# PICDevBoard-V1RevA.net
KiCad netlist of a schematic drawn in EAGLE
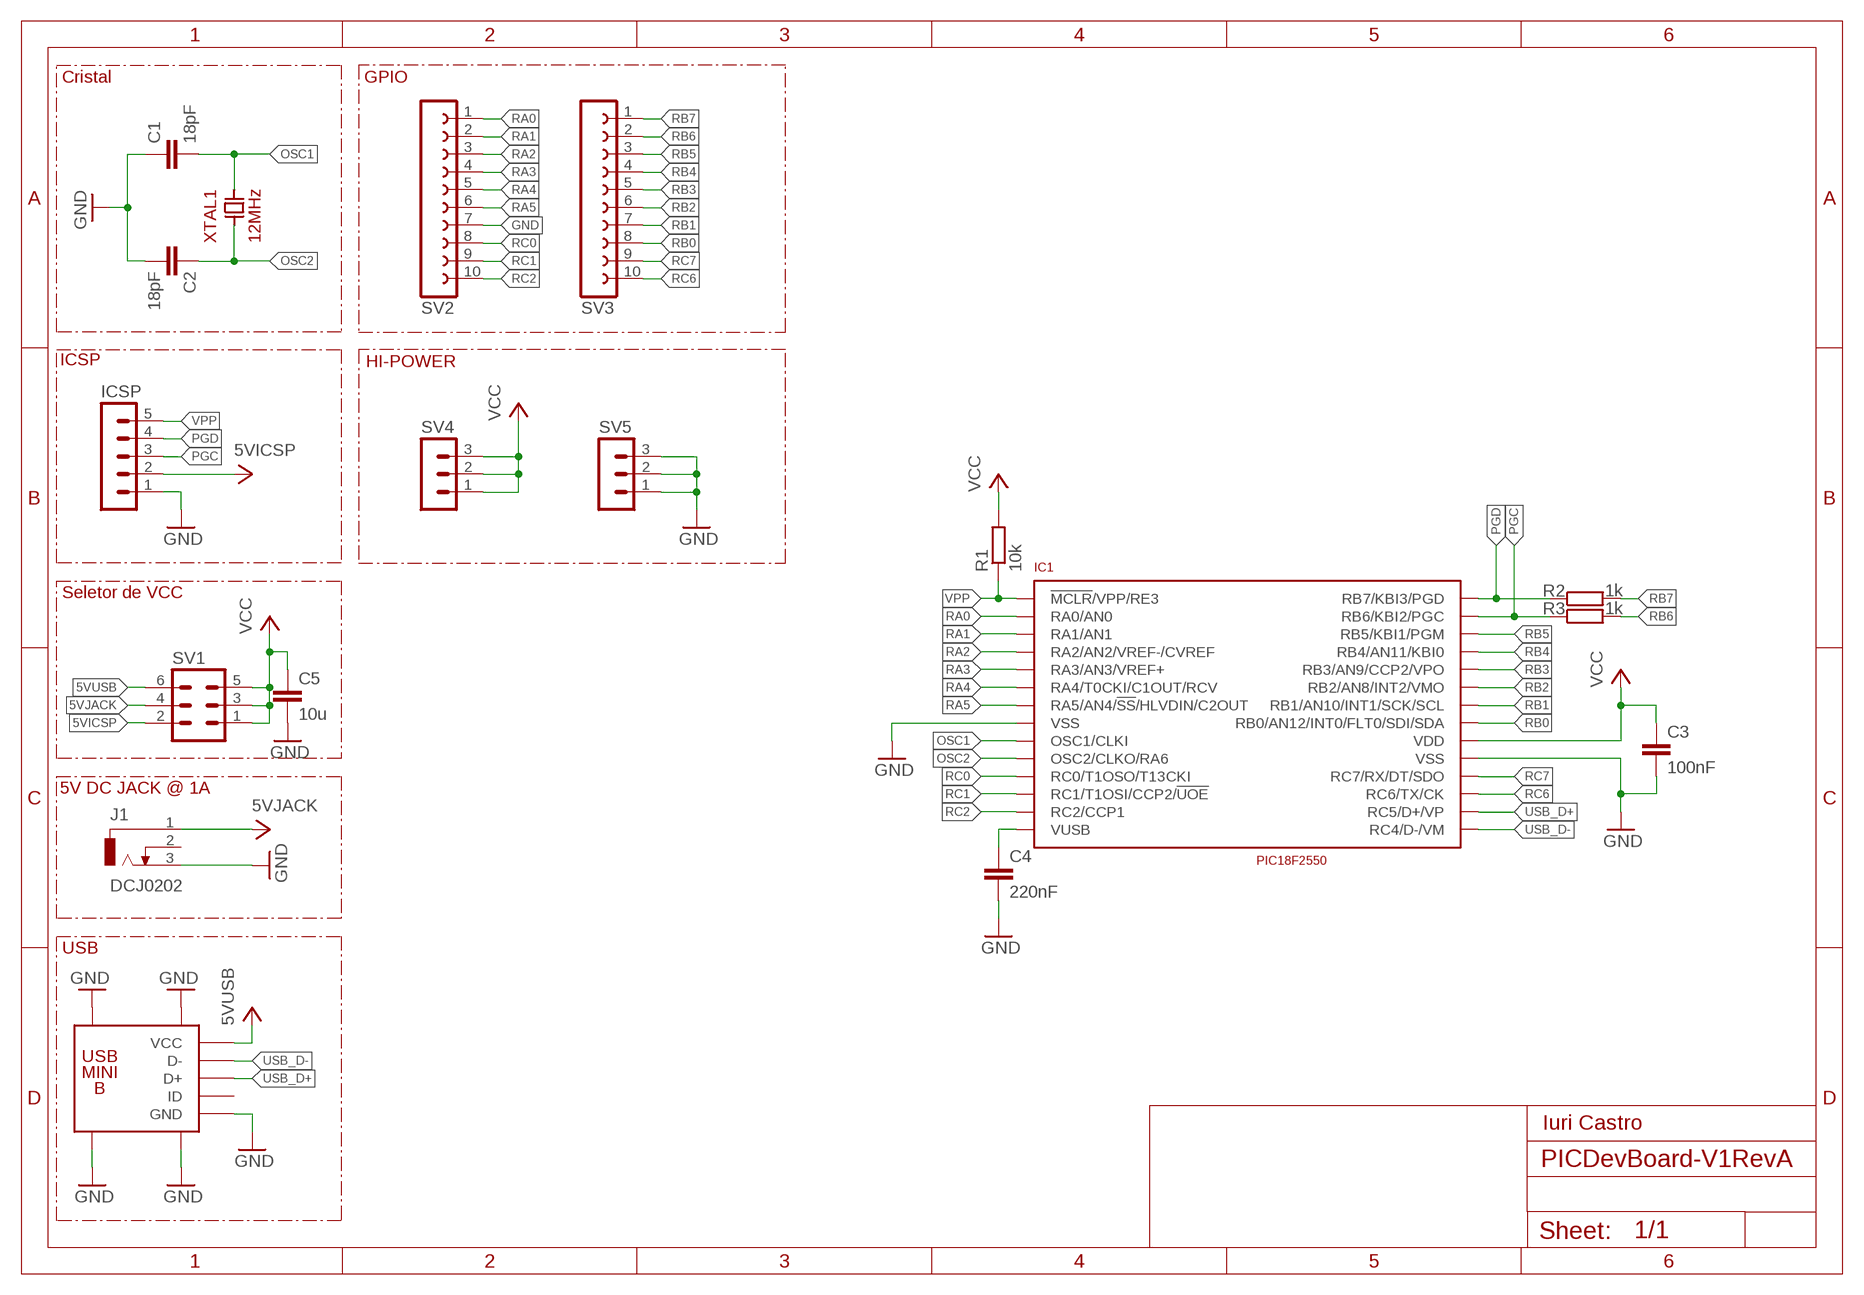
[diagram p0: schematic, sheet 1]

(export (version "E")
  (design (tool "Eeschema 10.0.6"))
  (components
    (comp (ref "C1")
      (value "18pF")
      (footprint "eagle-import:C0805")
      (libsource (lib "eagle-import") (part "C-EUC0805"))
    )
    (comp (ref "C2")
      (value "18pF")
      (footprint "eagle-import:C0805")
      (libsource (lib "eagle-import") (part "C-EUC0805"))
    )
    (comp (ref "C3")
      (value "100nF")
      (footprint "eagle-import:C0805")
      (libsource (lib "eagle-import") (part "C-EUC0805"))
    )
    (comp (ref "C4")
      (value "220nF")
      (footprint "eagle-import:C0805")
      (libsource (lib "eagle-import") (part "C-EUC0805"))
    )
    (comp (ref "C5")
      (value "10u")
      (footprint "eagle-import:C0805")
      (libsource (lib "eagle-import") (part "C-EUC0805"))
    )
    (comp (ref "IC1")
      (value "PIC18F2550")
      (footprint "eagle-import:DIL28-3")
      (libsource (lib "eagle-import") (part "PIC18F2550"))
    )
    (comp (ref "ICSP")
      (value "MA05-1")
      (footprint "eagle-import:MA05-1")
      (libsource (lib "eagle-import") (part "MA05-1"))
    )
    (comp (ref "J1")
      (value "DCJ0202")
      (footprint "eagle-import:DCJ0202")
      (libsource (lib "eagle-import") (part "DCJ0202"))
    )
    (comp (ref "R1")
      (value "10k")
      (footprint "eagle-import:R0805")
      (libsource (lib "eagle-import") (part "R-EU_R0805"))
    )
    (comp (ref "R2")
      (value "1k")
      (footprint "eagle-import:R0805")
      (libsource (lib "eagle-import") (part "R-EU_R0805"))
    )
    (comp (ref "R3")
      (value "1k")
      (footprint "eagle-import:R0805")
      (libsource (lib "eagle-import") (part "R-EU_R0805"))
    )
    (comp (ref "SV1")
      (value "MA03-2")
      (footprint "eagle-import:MA03-2")
      (libsource (lib "eagle-import") (part "MA03-2"))
    )
    (comp (ref "SV2")
      (value "FE10-1")
      (footprint "eagle-import:FE10")
      (libsource (lib "eagle-import") (part "FE10-1"))
    )
    (comp (ref "SV3")
      (value "FE10-1")
      (footprint "eagle-import:FE10")
      (libsource (lib "eagle-import") (part "FE10-1"))
    )
    (comp (ref "SV4")
      (value "MA03-1")
      (footprint "eagle-import:MA03-1")
      (libsource (lib "eagle-import") (part "MA03-1"))
    )
    (comp (ref "SV5")
      (value "MA03-1")
      (footprint "eagle-import:MA03-1")
      (libsource (lib "eagle-import") (part "MA03-1"))
    )
    (comp (ref "USB1")
      (value "USB-MINI-B")
      (footprint "eagle-import:DX2R005HN2E700")
      (libsource (lib "eagle-import") (part "USB-MINI-B"))
    )
    (comp (ref "XTAL1")
      (value "12MHz")
      (footprint "eagle-import:HC49-S")
      (libsource (lib "eagle-import") (part "HC49-S"))
    )
  )
  (nets
    (net (code "1") (name "5VICSP") (class "Default")
      (node (ref "ICSP") (pin "2") (pinfunction "2_2") (pintype "passive"))
      (node (ref "SV1") (pin "2") (pinfunction "2_2") (pintype "passive"))
    )
    (net (code "2") (name "5VJACK") (class "Default")
      (node (ref "J1") (pin "1") (pinfunction "1_1") (pintype "passive"))
      (node (ref "SV1") (pin "4") (pinfunction "4_4") (pintype "passive"))
    )
    (net (code "3") (name "5VUSB") (class "Default")
      (node (ref "SV1") (pin "6") (pinfunction "6_6") (pintype "passive"))
      (node (ref "USB1") (pin "P$1") (pinfunction "VCC_P$1") (pintype "bidirectional"))
    )
    (net (code "4") (name "GND") (class "Default")
      (node (ref "C1") (pin "1") (pinfunction "1_1") (pintype "passive"))
      (node (ref "C2") (pin "2") (pinfunction "2_2") (pintype "passive"))
      (node (ref "C3") (pin "2") (pinfunction "2_2") (pintype "passive"))
      (node (ref "C4") (pin "2") (pinfunction "2_2") (pintype "passive"))
      (node (ref "C5") (pin "2") (pinfunction "2_2") (pintype "passive"))
      (node (ref "IC1") (pin "19") (pinfunction "VSS_19") (pintype "bidirectional"))
      (node (ref "IC1") (pin "8") (pinfunction "VSS_8") (pintype "bidirectional"))
      (node (ref "ICSP") (pin "1") (pinfunction "1_1") (pintype "passive"))
      (node (ref "J1") (pin "3") (pinfunction "3_3") (pintype "passive"))
      (node (ref "SV2") (pin "7") (pinfunction "7_7") (pintype "passive"))
      (node (ref "SV5") (pin "1") (pinfunction "1_1") (pintype "passive"))
      (node (ref "SV5") (pin "2") (pinfunction "2_2") (pintype "passive"))
      (node (ref "SV5") (pin "3") (pinfunction "3_3") (pintype "passive"))
      (node (ref "USB1") (pin "P$5") (pinfunction "GND_P$5") (pintype "bidirectional"))
      (node (ref "USB1") (pin "P$6") (pinfunction "GND_P$6") (pintype "bidirectional"))
      (node (ref "USB1") (pin "P$7") (pinfunction "GND_P$7") (pintype "bidirectional"))
      (node (ref "USB1") (pin "P$8") (pinfunction "GND_P$8") (pintype "bidirectional"))
      (node (ref "USB1") (pin "P$9") (pinfunction "GND_P$9") (pintype "bidirectional"))
    )
    (net (code "5") (name "Net-(IC1-VUSB)") (class "Default")
      (node (ref "C4") (pin "1") (pinfunction "1_1") (pintype "passive"))
      (node (ref "IC1") (pin "14") (pinfunction "VUSB_14") (pintype "bidirectional"))
    )
    (net (code "6") (name "OSC1") (class "Default")
      (node (ref "C1") (pin "2") (pinfunction "2_2") (pintype "passive"))
      (node (ref "IC1") (pin "9") (pinfunction "OSC1/CLKI_9") (pintype "bidirectional"))
      (node (ref "XTAL1") (pin "P$2") (pinfunction "P$2_P$2") (pintype "bidirectional"))
    )
    (net (code "7") (name "OSC2") (class "Default")
      (node (ref "C2") (pin "1") (pinfunction "1_1") (pintype "passive"))
      (node (ref "IC1") (pin "10") (pinfunction "OSC2/CLKO/RA6_10") (pintype "bidirectional"))
      (node (ref "XTAL1") (pin "P$1") (pinfunction "P$1_P$1") (pintype "bidirectional"))
    )
    (net (code "8") (name "PGC") (class "Default")
      (node (ref "IC1") (pin "27") (pinfunction "RB6/KBI2/PGC_27") (pintype "bidirectional"))
      (node (ref "ICSP") (pin "3") (pinfunction "3_3") (pintype "passive"))
      (node (ref "R3") (pin "1") (pinfunction "1_1") (pintype "passive"))
    )
    (net (code "9") (name "PGD") (class "Default")
      (node (ref "IC1") (pin "28") (pinfunction "RB7/KBI3/PGD_28") (pintype "bidirectional"))
      (node (ref "ICSP") (pin "4") (pinfunction "4_4") (pintype "passive"))
      (node (ref "R2") (pin "1") (pinfunction "1_1") (pintype "passive"))
    )
    (net (code "10") (name "RA0") (class "Default")
      (node (ref "IC1") (pin "2") (pinfunction "RA0/AN0_2") (pintype "bidirectional"))
      (node (ref "SV2") (pin "1") (pinfunction "1_1") (pintype "passive"))
    )
    (net (code "11") (name "RA1") (class "Default")
      (node (ref "IC1") (pin "3") (pinfunction "RA1/AN1_3") (pintype "bidirectional"))
      (node (ref "SV2") (pin "2") (pinfunction "2_2") (pintype "passive"))
    )
    (net (code "12") (name "RA2") (class "Default")
      (node (ref "IC1") (pin "4") (pinfunction "RA2/AN2/VREF-/CVREF_4") (pintype "bidirectional"))
      (node (ref "SV2") (pin "3") (pinfunction "3_3") (pintype "passive"))
    )
    (net (code "13") (name "RA3") (class "Default")
      (node (ref "IC1") (pin "5") (pinfunction "RA3/AN3/VREF+_5") (pintype "bidirectional"))
      (node (ref "SV2") (pin "4") (pinfunction "4_4") (pintype "passive"))
    )
    (net (code "14") (name "RA4") (class "Default")
      (node (ref "IC1") (pin "6") (pinfunction "RA4/T0CKI/C1OUT/RCV_6") (pintype "bidirectional"))
      (node (ref "SV2") (pin "5") (pinfunction "5_5") (pintype "passive"))
    )
    (net (code "15") (name "RA5") (class "Default")
      (node (ref "IC1") (pin "7") (pinfunction "RA5/AN4/~{SS}/HLVDIN/C2OUT_7") (pintype "bidirectional"))
      (node (ref "SV2") (pin "6") (pinfunction "6_6") (pintype "passive"))
    )
    (net (code "16") (name "RB0") (class "Default")
      (node (ref "IC1") (pin "21") (pinfunction "RB0/AN12/INT0/FLT0/SDI/SDA_21") (pintype "bidirectional"))
      (node (ref "SV3") (pin "8") (pinfunction "8_8") (pintype "passive"))
    )
    (net (code "17") (name "RB1") (class "Default")
      (node (ref "IC1") (pin "22") (pinfunction "RB1/AN10/INT1/SCK/SCL_22") (pintype "bidirectional"))
      (node (ref "SV3") (pin "7") (pinfunction "7_7") (pintype "passive"))
    )
    (net (code "18") (name "RB2") (class "Default")
      (node (ref "IC1") (pin "23") (pinfunction "RB2/AN8/INT2/VMO_23") (pintype "bidirectional"))
      (node (ref "SV3") (pin "6") (pinfunction "6_6") (pintype "passive"))
    )
    (net (code "19") (name "RB3") (class "Default")
      (node (ref "IC1") (pin "24") (pinfunction "RB3/AN9/CCP2/VPO_24") (pintype "bidirectional"))
      (node (ref "SV3") (pin "5") (pinfunction "5_5") (pintype "passive"))
    )
    (net (code "20") (name "RB4") (class "Default")
      (node (ref "IC1") (pin "25") (pinfunction "RB4/AN11/KBI0_25") (pintype "bidirectional"))
      (node (ref "SV3") (pin "4") (pinfunction "4_4") (pintype "passive"))
    )
    (net (code "21") (name "RB5") (class "Default")
      (node (ref "IC1") (pin "26") (pinfunction "RB5/KBI1/PGM_26") (pintype "bidirectional"))
      (node (ref "SV3") (pin "3") (pinfunction "3_3") (pintype "passive"))
    )
    (net (code "22") (name "RB6") (class "Default")
      (node (ref "R3") (pin "2") (pinfunction "2_2") (pintype "passive"))
      (node (ref "SV3") (pin "2") (pinfunction "2_2") (pintype "passive"))
    )
    (net (code "23") (name "RB7") (class "Default")
      (node (ref "R2") (pin "2") (pinfunction "2_2") (pintype "passive"))
      (node (ref "SV3") (pin "1") (pinfunction "1_1") (pintype "passive"))
    )
    (net (code "24") (name "RC0") (class "Default")
      (node (ref "IC1") (pin "11") (pinfunction "RC0/T1OSO/T13CKI_11") (pintype "bidirectional"))
      (node (ref "SV2") (pin "8") (pinfunction "8_8") (pintype "passive"))
    )
    (net (code "25") (name "RC1") (class "Default")
      (node (ref "IC1") (pin "12") (pinfunction "RC1/T1OSI/CCP2/~{UOE}_12") (pintype "bidirectional"))
      (node (ref "SV2") (pin "9") (pinfunction "9_9") (pintype "passive"))
    )
    (net (code "26") (name "RC2") (class "Default")
      (node (ref "IC1") (pin "13") (pinfunction "RC2/CCP1_13") (pintype "bidirectional"))
      (node (ref "SV2") (pin "10") (pinfunction "10_10") (pintype "passive"))
    )
    (net (code "27") (name "RC6") (class "Default")
      (node (ref "IC1") (pin "17") (pinfunction "RC6/TX/CK_17") (pintype "bidirectional"))
      (node (ref "SV3") (pin "10") (pinfunction "10_10") (pintype "passive"))
    )
    (net (code "28") (name "RC7") (class "Default")
      (node (ref "IC1") (pin "18") (pinfunction "RC7/RX/DT/SDO_18") (pintype "bidirectional"))
      (node (ref "SV3") (pin "9") (pinfunction "9_9") (pintype "passive"))
    )
    (net (code "29") (name "USB_D+") (class "Default")
      (node (ref "IC1") (pin "16") (pinfunction "RC5/D+/VP_16") (pintype "bidirectional"))
      (node (ref "USB1") (pin "P$3") (pinfunction "D+_P$3") (pintype "bidirectional"))
    )
    (net (code "30") (name "USB_D-") (class "Default")
      (node (ref "IC1") (pin "15") (pinfunction "RC4/D-/VM_15") (pintype "bidirectional"))
      (node (ref "USB1") (pin "P$2") (pinfunction "D-_P$2") (pintype "bidirectional"))
    )
    (net (code "31") (name "VCC") (class "Default")
      (node (ref "C3") (pin "1") (pinfunction "1_1") (pintype "passive"))
      (node (ref "C5") (pin "1") (pinfunction "1_1") (pintype "passive"))
      (node (ref "IC1") (pin "20") (pinfunction "VDD_20") (pintype "bidirectional"))
      (node (ref "R1") (pin "2") (pinfunction "2_2") (pintype "passive"))
      (node (ref "SV1") (pin "1") (pinfunction "1_1") (pintype "passive"))
      (node (ref "SV1") (pin "3") (pinfunction "3_3") (pintype "passive"))
      (node (ref "SV1") (pin "5") (pinfunction "5_5") (pintype "passive"))
      (node (ref "SV4") (pin "1") (pinfunction "1_1") (pintype "passive"))
      (node (ref "SV4") (pin "2") (pinfunction "2_2") (pintype "passive"))
      (node (ref "SV4") (pin "3") (pinfunction "3_3") (pintype "passive"))
    )
    (net (code "32") (name "VPP") (class "Default")
      (node (ref "IC1") (pin "1") (pinfunction "~{MCLR}/VPP/RE3_1") (pintype "bidirectional"))
      (node (ref "ICSP") (pin "5") (pinfunction "5_5") (pintype "passive"))
      (node (ref "R1") (pin "1") (pinfunction "1_1") (pintype "passive"))
    )
    (net (code "33") (name "unconnected-(J1-Pad2)") (class "Default")
      (node (ref "J1") (pin "2") (pinfunction "2_2") (pintype "passive"))
    )
    (net (code "34") (name "unconnected-(USB1-ID-PadP$4)") (class "Default")
      (node (ref "USB1") (pin "P$4") (pinfunction "ID_P$4") (pintype "bidirectional"))
    )
  )
)
